# AJH_as3310_DUAL_ASR_03_4hp.net
KiCad netlist of a schematic drawn in EAGLE
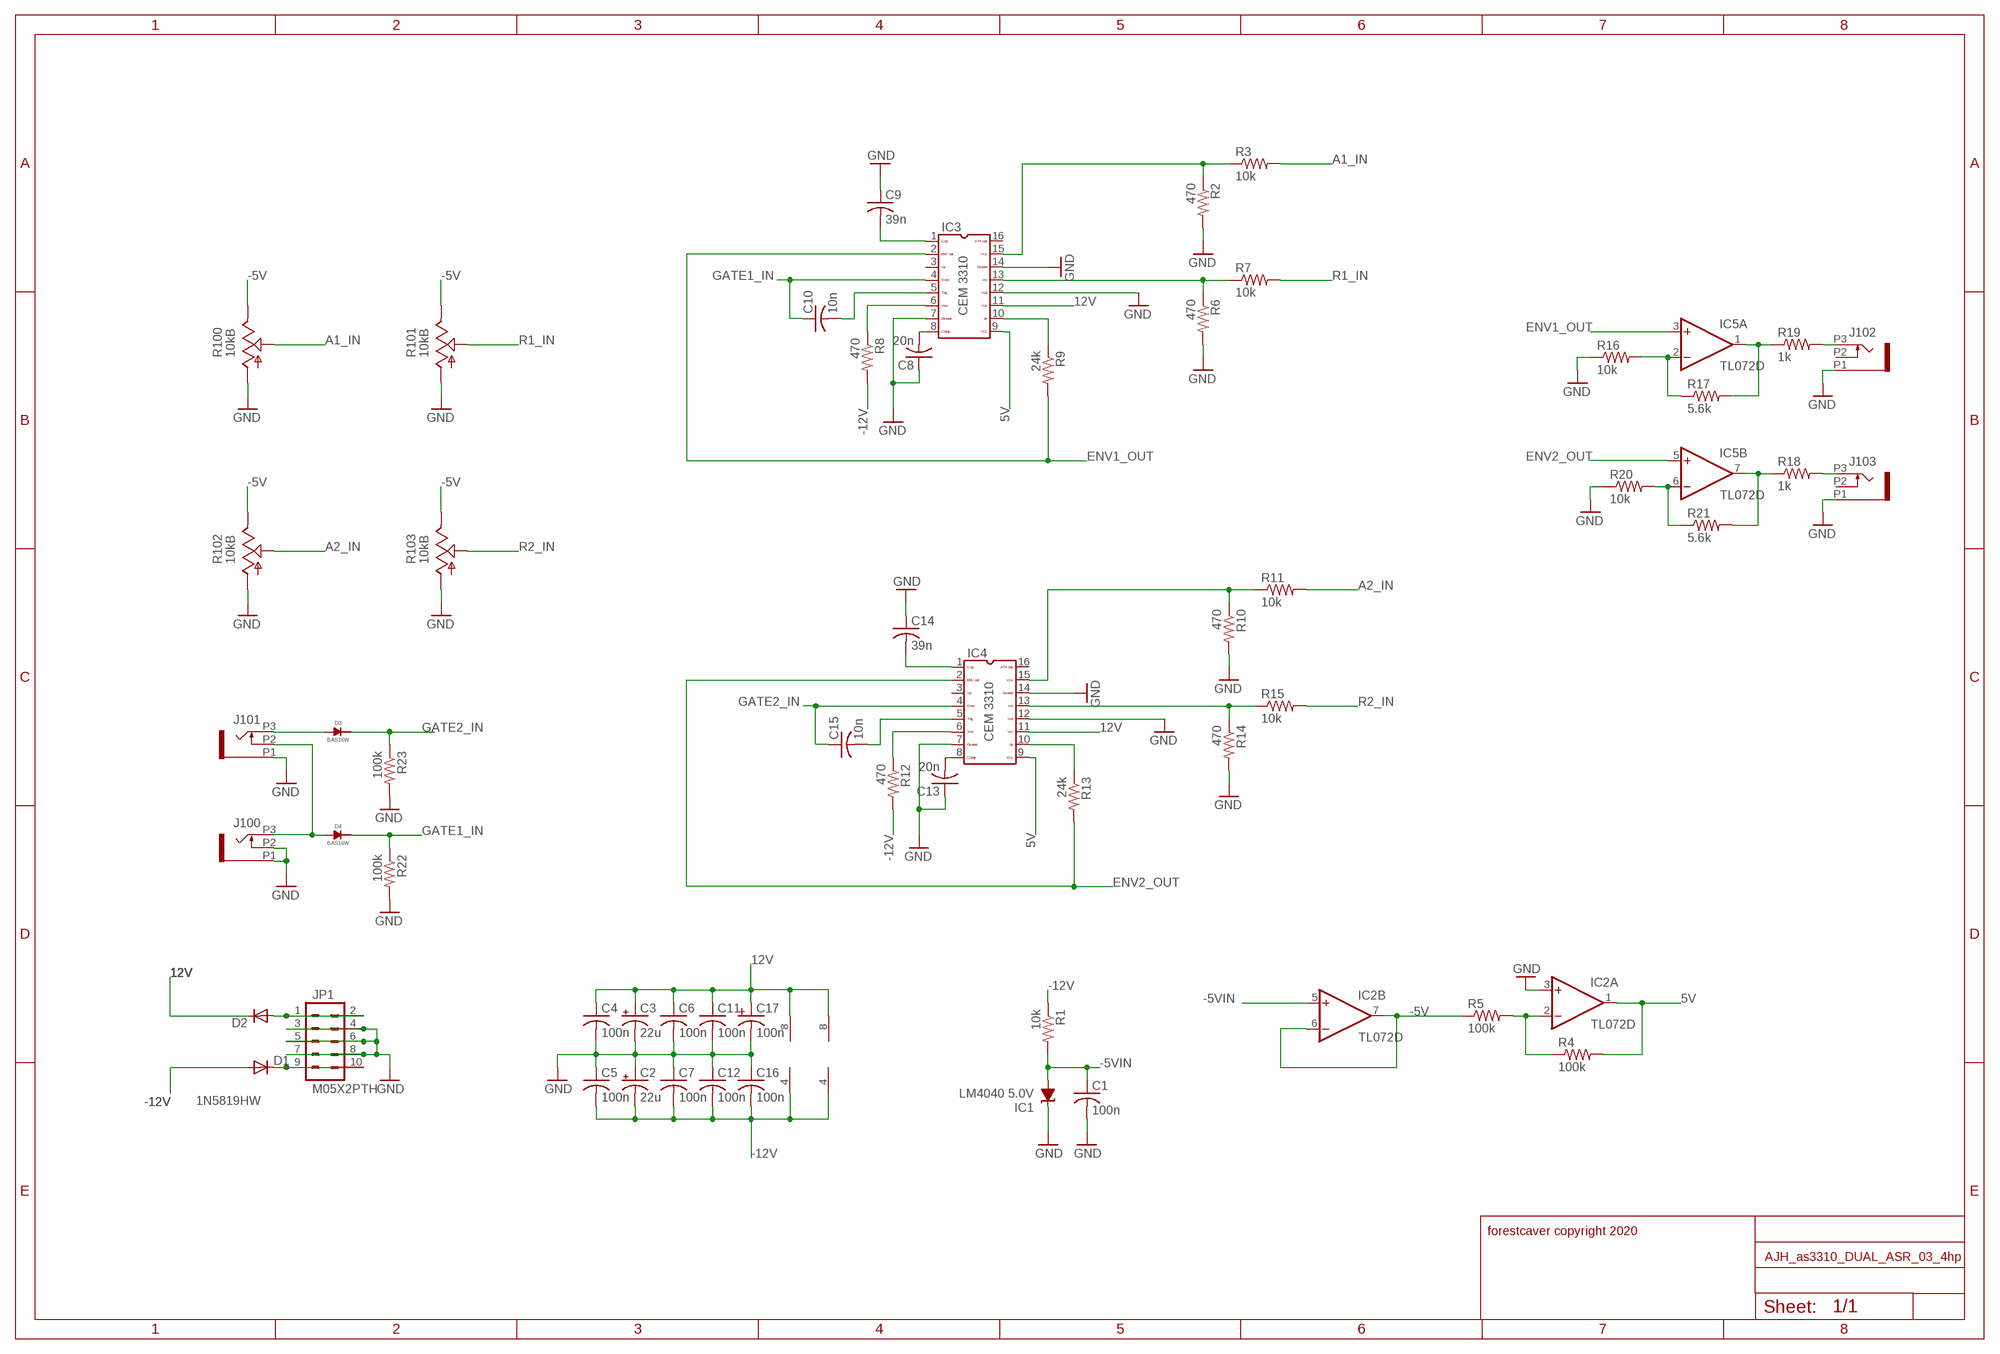
[diagram p0: schematic, sheet 1]

(export (version "E")
  (design (tool "Eeschema 10.0.6"))
  (components
    (comp (ref "C1")
      (value "100n")
      (footprint "eagle-import:C0603")
      (libsource (lib "eagle-import") (part "C-USC0603"))
    )
    (comp (ref "C2")
      (value "22u")
      (footprint "eagle-import:PANASONIC_B")
      (libsource (lib "eagle-import") (part "CPOL-USB"))
    )
    (comp (ref "C3")
      (value "22u")
      (footprint "eagle-import:PANASONIC_B")
      (libsource (lib "eagle-import") (part "CPOL-USB"))
    )
    (comp (ref "C4")
      (value "100n")
      (footprint "eagle-import:C0603")
      (libsource (lib "eagle-import") (part "C-USC0603"))
    )
    (comp (ref "C5")
      (value "100n")
      (footprint "eagle-import:C0603")
      (libsource (lib "eagle-import") (part "C-USC0603"))
    )
    (comp (ref "C6")
      (value "100n")
      (footprint "eagle-import:C0603")
      (libsource (lib "eagle-import") (part "C-USC0603"))
    )
    (comp (ref "C7")
      (value "100n")
      (footprint "eagle-import:C0603")
      (libsource (lib "eagle-import") (part "C-USC0603"))
    )
    (comp (ref "C8")
      (value "20n")
      (footprint "eagle-import:C0603")
      (libsource (lib "eagle-import") (part "C-USC0603"))
    )
    (comp (ref "C9")
      (value "39n")
      (footprint "eagle-import:C0603")
      (libsource (lib "eagle-import") (part "C-USC0603"))
    )
    (comp (ref "C10")
      (value "10n")
      (footprint "eagle-import:C0603")
      (libsource (lib "eagle-import") (part "C-USC0603"))
    )
    (comp (ref "C11")
      (value "100n")
      (footprint "eagle-import:C0603")
      (libsource (lib "eagle-import") (part "C-USC0603"))
    )
    (comp (ref "C12")
      (value "100n")
      (footprint "eagle-import:C0603")
      (libsource (lib "eagle-import") (part "C-USC0603"))
    )
    (comp (ref "C13")
      (value "20n")
      (footprint "eagle-import:C0603")
      (libsource (lib "eagle-import") (part "C-USC0603"))
    )
    (comp (ref "C14")
      (value "39n")
      (footprint "eagle-import:C0603")
      (libsource (lib "eagle-import") (part "C-USC0603"))
    )
    (comp (ref "C15")
      (value "10n")
      (footprint "eagle-import:C0603")
      (libsource (lib "eagle-import") (part "C-USC0603"))
    )
    (comp (ref "C16")
      (value "100n")
      (footprint "eagle-import:C0603")
      (libsource (lib "eagle-import") (part "C-USC0603"))
    )
    (comp (ref "C17")
      (value "100n")
      (footprint "eagle-import:C0603")
      (libsource (lib "eagle-import") (part "C-USC0603"))
    )
    (comp (ref "D1")
      (value "1N5819HW")
      (footprint "eagle-import:SOD123")
      (libsource (lib "eagle-import") (part "DIODE-SOD123"))
    )
    (comp (ref "D2")
      (value "1N5819HW")
      (footprint "eagle-import:SOD123")
      (libsource (lib "eagle-import") (part "DIODE-SOD123"))
    )
    (comp (ref "D3")
      (value "BAS16W")
      (footprint "eagle-import:SOT-323")
      (libsource (lib "eagle-import") (part "BAS16W"))
    )
    (comp (ref "D4")
      (value "BAS16W")
      (footprint "eagle-import:SOT-323")
      (libsource (lib "eagle-import") (part "BAS16W"))
    )
    (comp (ref "IC1")
      (value "LM4040 5.0V")
      (footprint "eagle-import:DBZ_R-PDSO-G3")
      (libsource (lib "eagle-import") (part "LM4041DBZC12"))
    )
    (comp (ref "IC2")
      (value "TL072D")
      (footprint "eagle-import:SO08")
      (libsource (lib "eagle-import") (part "TL072D"))
    )
    (comp (ref "IC3")
      (value "CEM3310SOIC16")
      (footprint "eagle-import:SO16")
      (libsource (lib "eagle-import") (part "CEM3310SOIC16"))
    )
    (comp (ref "IC4")
      (value "CEM3310SOIC16")
      (footprint "eagle-import:SO16")
      (libsource (lib "eagle-import") (part "CEM3310SOIC16"))
    )
    (comp (ref "IC5")
      (value "TL072D")
      (footprint "eagle-import:SO08")
      (libsource (lib "eagle-import") (part "TL072D"))
    )
    (comp (ref "J100")
      (value "PJ301_THONKICONN6")
      (footprint "eagle-import:WQP_PJ_301M6")
      (libsource (lib "eagle-import") (part "PJ301_THONKICONN6"))
    )
    (comp (ref "J101")
      (value "PJ301_THONKICONN6")
      (footprint "eagle-import:WQP_PJ_301M6")
      (libsource (lib "eagle-import") (part "PJ301_THONKICONN6"))
    )
    (comp (ref "J102")
      (value "PJ301_THONKICONN6")
      (footprint "eagle-import:WQP_PJ_301M6")
      (libsource (lib "eagle-import") (part "PJ301_THONKICONN6"))
    )
    (comp (ref "J103")
      (value "PJ301_THONKICONN6")
      (footprint "eagle-import:WQP_PJ_301M6")
      (libsource (lib "eagle-import") (part "PJ301_THONKICONN6"))
    )
    (comp (ref "JP1")
      (value "M05X2PTH")
      (footprint "eagle-import:AVR_ICSP")
      (libsource (lib "eagle-import") (part "M05X2PTH"))
    )
    (comp (ref "R1")
      (value "10k")
      (footprint "eagle-import:R0603")
      (libsource (lib "eagle-import") (part "R-US_R0603"))
    )
    (comp (ref "R2")
      (value "470")
      (footprint "eagle-import:R0603")
      (libsource (lib "eagle-import") (part "R-US_R0603"))
    )
    (comp (ref "R3")
      (value "10k")
      (footprint "eagle-import:R0603")
      (libsource (lib "eagle-import") (part "R-US_R0603"))
    )
    (comp (ref "R4")
      (value "100k")
      (footprint "eagle-import:R0603")
      (libsource (lib "eagle-import") (part "R-US_R0603"))
    )
    (comp (ref "R5")
      (value "100k")
      (footprint "eagle-import:R0603")
      (libsource (lib "eagle-import") (part "R-US_R0603"))
    )
    (comp (ref "R6")
      (value "470")
      (footprint "eagle-import:R0603")
      (libsource (lib "eagle-import") (part "R-US_R0603"))
    )
    (comp (ref "R7")
      (value "10k")
      (footprint "eagle-import:R0603")
      (libsource (lib "eagle-import") (part "R-US_R0603"))
    )
    (comp (ref "R8")
      (value "470")
      (footprint "eagle-import:R0603")
      (libsource (lib "eagle-import") (part "R-US_R0603"))
    )
    (comp (ref "R9")
      (value "24k")
      (footprint "eagle-import:R0603")
      (libsource (lib "eagle-import") (part "R-US_R0603"))
    )
    (comp (ref "R10")
      (value "470")
      (footprint "eagle-import:R0603")
      (libsource (lib "eagle-import") (part "R-US_R0603"))
    )
    (comp (ref "R11")
      (value "10k")
      (footprint "eagle-import:R0603")
      (libsource (lib "eagle-import") (part "R-US_R0603"))
    )
    (comp (ref "R12")
      (value "470")
      (footprint "eagle-import:R0603")
      (libsource (lib "eagle-import") (part "R-US_R0603"))
    )
    (comp (ref "R13")
      (value "24k")
      (footprint "eagle-import:R0603")
      (libsource (lib "eagle-import") (part "R-US_R0603"))
    )
    (comp (ref "R14")
      (value "470")
      (footprint "eagle-import:R0603")
      (libsource (lib "eagle-import") (part "R-US_R0603"))
    )
    (comp (ref "R15")
      (value "10k")
      (footprint "eagle-import:R0603")
      (libsource (lib "eagle-import") (part "R-US_R0603"))
    )
    (comp (ref "R16")
      (value "10k")
      (footprint "eagle-import:R0603")
      (libsource (lib "eagle-import") (part "R-US_R0603"))
    )
    (comp (ref "R17")
      (value "5.6k")
      (footprint "eagle-import:R0603")
      (libsource (lib "eagle-import") (part "R-US_R0603"))
    )
    (comp (ref "R18")
      (value "1k")
      (footprint "eagle-import:R0603")
      (libsource (lib "eagle-import") (part "R-US_R0603"))
    )
    (comp (ref "R19")
      (value "1k")
      (footprint "eagle-import:R0603")
      (libsource (lib "eagle-import") (part "R-US_R0603"))
    )
    (comp (ref "R20")
      (value "10k")
      (footprint "eagle-import:R0603")
      (libsource (lib "eagle-import") (part "R-US_R0603"))
    )
    (comp (ref "R21")
      (value "5.6k")
      (footprint "eagle-import:R0603")
      (libsource (lib "eagle-import") (part "R-US_R0603"))
    )
    (comp (ref "R22")
      (value "100k")
      (footprint "eagle-import:R0603")
      (libsource (lib "eagle-import") (part "R-US_R0603"))
    )
    (comp (ref "R23")
      (value "100k")
      (footprint "eagle-import:R0603")
      (libsource (lib "eagle-import") (part "R-US_R0603"))
    )
    (comp (ref "R100")
      (value "10kB")
      (footprint "eagle-import:ALPS_POT_VERTICAL")
      (libsource (lib "eagle-import") (part "POT_USVERTICAL"))
    )
    (comp (ref "R101")
      (value "10kB")
      (footprint "eagle-import:ALPS_POT_VERTICAL")
      (libsource (lib "eagle-import") (part "POT_USVERTICAL"))
    )
    (comp (ref "R102")
      (value "10kB")
      (footprint "eagle-import:ALPS_POT_VERTICAL")
      (libsource (lib "eagle-import") (part "POT_USVERTICAL"))
    )
    (comp (ref "R103")
      (value "10kB")
      (footprint "eagle-import:ALPS_POT_VERTICAL")
      (libsource (lib "eagle-import") (part "POT_USVERTICAL"))
    )
  )
  (nets
    (net (code "1") (name "/-5V") (class "Default")
      (node (ref "IC2") (pin "6") (pinfunction "-IN_6") (pintype "input"))
      (node (ref "IC2") (pin "7") (pinfunction "OUT_7") (pintype "output"))
      (node (ref "R100") (pin "P$1") (pinfunction "E_P$1") (pintype "passive"))
      (node (ref "R101") (pin "P$1") (pinfunction "E_P$1") (pintype "passive"))
      (node (ref "R102") (pin "P$1") (pinfunction "E_P$1") (pintype "passive"))
      (node (ref "R103") (pin "P$1") (pinfunction "E_P$1") (pintype "passive"))
      (node (ref "R5") (pin "1") (pinfunction "1_1") (pintype "passive"))
    )
    (net (code "2") (name "/-5VIN") (class "Default")
      (node (ref "C1") (pin "1") (pinfunction "1_1") (pintype "passive"))
      (node (ref "IC1") (pin "2") (pinfunction "A_2") (pintype "passive"))
      (node (ref "IC2") (pin "5") (pinfunction "+IN_5") (pintype "input"))
      (node (ref "R1") (pin "2") (pinfunction "2_2") (pintype "passive"))
    )
    (net (code "3") (name "/-12V") (class "Default")
      (node (ref "C12") (pin "2") (pinfunction "2_2") (pintype "passive"))
      (node (ref "C16") (pin "2") (pinfunction "2_2") (pintype "passive"))
      (node (ref "C2") (pin "-") (pinfunction "-_-") (pintype "passive"))
      (node (ref "C5") (pin "2") (pinfunction "2_2") (pintype "passive"))
      (node (ref "C7") (pin "2") (pinfunction "2_2") (pintype "passive"))
      (node (ref "D1") (pin "A") (pinfunction "A_A") (pintype "passive"))
      (node (ref "IC2") (pin "4") (pinfunction "V-_4") (pintype "power_in"))
      (node (ref "IC5") (pin "4") (pinfunction "V-_4") (pintype "power_in"))
      (node (ref "R1") (pin "1") (pinfunction "1_1") (pintype "passive"))
      (node (ref "R12") (pin "2") (pinfunction "2_2") (pintype "passive"))
      (node (ref "R8") (pin "2") (pinfunction "2_2") (pintype "passive"))
    )
    (net (code "4") (name "/5V") (class "Default")
      (node (ref "IC2") (pin "1") (pinfunction "OUT_1") (pintype "output"))
      (node (ref "IC3") (pin "9") (pinfunction "9_9") (pintype "power_in"))
      (node (ref "IC4") (pin "9") (pinfunction "9_9") (pintype "power_in"))
      (node (ref "R4") (pin "2") (pinfunction "2_2") (pintype "passive"))
    )
    (net (code "5") (name "/12V") (class "Default")
      (node (ref "C11") (pin "1") (pinfunction "1_1") (pintype "passive"))
      (node (ref "C17") (pin "1") (pinfunction "1_1") (pintype "passive"))
      (node (ref "C3") (pin "+") (pinfunction "+_+") (pintype "passive"))
      (node (ref "C4") (pin "1") (pinfunction "1_1") (pintype "passive"))
      (node (ref "C6") (pin "1") (pinfunction "1_1") (pintype "passive"))
      (node (ref "D2") (pin "C") (pinfunction "C_C") (pintype "passive"))
      (node (ref "IC2") (pin "8") (pinfunction "V+_8") (pintype "power_in"))
      (node (ref "IC3") (pin "11") (pinfunction "11_11") (pintype "power_in"))
      (node (ref "IC4") (pin "11") (pinfunction "11_11") (pintype "power_in"))
      (node (ref "IC5") (pin "8") (pinfunction "V+_8") (pintype "power_in"))
    )
    (net (code "6") (name "/A1_IN") (class "Default")
      (node (ref "R100") (pin "P$2") (pinfunction "S_P$2") (pintype "passive"))
      (node (ref "R3") (pin "2") (pinfunction "2_2") (pintype "passive"))
    )
    (net (code "7") (name "/A2_IN") (class "Default")
      (node (ref "R102") (pin "P$2") (pinfunction "S_P$2") (pintype "passive"))
      (node (ref "R11") (pin "2") (pinfunction "2_2") (pintype "passive"))
    )
    (net (code "8") (name "/ENV1_OUT") (class "Default")
      (node (ref "IC3") (pin "2") (pinfunction "2_2") (pintype "output"))
      (node (ref "IC5") (pin "3") (pinfunction "+IN_3") (pintype "input"))
      (node (ref "R9") (pin "2") (pinfunction "2_2") (pintype "passive"))
    )
    (net (code "9") (name "/ENV2_OUT") (class "Default")
      (node (ref "IC4") (pin "2") (pinfunction "2_2") (pintype "output"))
      (node (ref "IC5") (pin "5") (pinfunction "+IN_5") (pintype "input"))
      (node (ref "R13") (pin "2") (pinfunction "2_2") (pintype "passive"))
    )
    (net (code "10") (name "/GATE1_IN") (class "Default")
      (node (ref "C10") (pin "1") (pinfunction "1_1") (pintype "passive"))
      (node (ref "D4") (pin "CATHODE") (pinfunction "CATHODE_CATHODE") (pintype "bidirectional"))
      (node (ref "IC3") (pin "4") (pinfunction "4_4") (pintype "input"))
      (node (ref "R22") (pin "1") (pinfunction "1_1") (pintype "passive"))
    )
    (net (code "11") (name "/GATE2_IN") (class "Default")
      (node (ref "C15") (pin "1") (pinfunction "1_1") (pintype "passive"))
      (node (ref "D3") (pin "CATHODE") (pinfunction "CATHODE_CATHODE") (pintype "bidirectional"))
      (node (ref "IC4") (pin "4") (pinfunction "4_4") (pintype "input"))
      (node (ref "R23") (pin "1") (pinfunction "1_1") (pintype "passive"))
    )
    (net (code "12") (name "/R1_IN") (class "Default")
      (node (ref "R101") (pin "P$2") (pinfunction "S_P$2") (pintype "passive"))
      (node (ref "R7") (pin "2") (pinfunction "2_2") (pintype "passive"))
    )
    (net (code "13") (name "/R2_IN") (class "Default")
      (node (ref "R103") (pin "P$2") (pinfunction "S_P$2") (pintype "passive"))
      (node (ref "R15") (pin "2") (pinfunction "2_2") (pintype "passive"))
    )
    (net (code "14") (name "GND") (class "Default")
      (node (ref "C1") (pin "2") (pinfunction "2_2") (pintype "passive"))
      (node (ref "C11") (pin "2") (pinfunction "2_2") (pintype "passive"))
      (node (ref "C12") (pin "1") (pinfunction "1_1") (pintype "passive"))
      (node (ref "C13") (pin "1") (pinfunction "1_1") (pintype "passive"))
      (node (ref "C14") (pin "1") (pinfunction "1_1") (pintype "passive"))
      (node (ref "C16") (pin "1") (pinfunction "1_1") (pintype "passive"))
      (node (ref "C17") (pin "2") (pinfunction "2_2") (pintype "passive"))
      (node (ref "C2") (pin "+") (pinfunction "+_+") (pintype "passive"))
      (node (ref "C3") (pin "-") (pinfunction "-_-") (pintype "passive"))
      (node (ref "C4") (pin "2") (pinfunction "2_2") (pintype "passive"))
      (node (ref "C5") (pin "1") (pinfunction "1_1") (pintype "passive"))
      (node (ref "C6") (pin "2") (pinfunction "2_2") (pintype "passive"))
      (node (ref "C7") (pin "1") (pinfunction "1_1") (pintype "passive"))
      (node (ref "C8") (pin "1") (pinfunction "1_1") (pintype "passive"))
      (node (ref "C9") (pin "1") (pinfunction "1_1") (pintype "passive"))
      (node (ref "IC1") (pin "1") (pinfunction "C_1") (pintype "passive"))
      (node (ref "IC2") (pin "3") (pinfunction "+IN_3") (pintype "input"))
      (node (ref "IC3") (pin "12") (pinfunction "12_12") (pintype "power_in"))
      (node (ref "IC3") (pin "14") (pinfunction "14_14") (pintype "power_in"))
      (node (ref "IC3") (pin "7") (pinfunction "7_7") (pintype "power_in"))
      (node (ref "IC4") (pin "12") (pinfunction "12_12") (pintype "power_in"))
      (node (ref "IC4") (pin "14") (pinfunction "14_14") (pintype "power_in"))
      (node (ref "IC4") (pin "7") (pinfunction "7_7") (pintype "power_in"))
      (node (ref "J100") (pin "P1") (pinfunction "1_P1") (pintype "passive"))
      (node (ref "J100") (pin "P2") (pinfunction "2_P2") (pintype "passive"))
      (node (ref "J101") (pin "P1") (pinfunction "1_P1") (pintype "passive"))
      (node (ref "J102") (pin "P1") (pinfunction "1_P1") (pintype "passive"))
      (node (ref "J103") (pin "P1") (pinfunction "1_P1") (pintype "passive"))
      (node (ref "JP1") (pin "3") (pinfunction "3_3") (pintype "passive"))
      (node (ref "JP1") (pin "4") (pinfunction "4_4") (pintype "passive"))
      (node (ref "JP1") (pin "5") (pinfunction "5_5") (pintype "passive"))
      (node (ref "JP1") (pin "6") (pinfunction "6_6") (pintype "passive"))
      (node (ref "JP1") (pin "7") (pinfunction "7_7") (pintype "passive"))
      (node (ref "JP1") (pin "8") (pinfunction "8_8") (pintype "passive"))
      (node (ref "R10") (pin "2") (pinfunction "2_2") (pintype "passive"))
      (node (ref "R100") (pin "P$3") (pinfunction "A_P$3") (pintype "passive"))
      (node (ref "R101") (pin "P$3") (pinfunction "A_P$3") (pintype "passive"))
      (node (ref "R102") (pin "P$3") (pinfunction "A_P$3") (pintype "passive"))
      (node (ref "R103") (pin "P$3") (pinfunction "A_P$3") (pintype "passive"))
      (node (ref "R14") (pin "2") (pinfunction "2_2") (pintype "passive"))
      (node (ref "R16") (pin "1") (pinfunction "1_1") (pintype "passive"))
      (node (ref "R2") (pin "2") (pinfunction "2_2") (pintype "passive"))
      (node (ref "R20") (pin "1") (pinfunction "1_1") (pintype "passive"))
      (node (ref "R22") (pin "2") (pinfunction "2_2") (pintype "passive"))
      (node (ref "R23") (pin "2") (pinfunction "2_2") (pintype "passive"))
      (node (ref "R6") (pin "2") (pinfunction "2_2") (pintype "passive"))
    )
    (net (code "15") (name "Net-(C8-Pad2)") (class "Default")
      (node (ref "C8") (pin "2") (pinfunction "2_2") (pintype "passive"))
      (node (ref "IC3") (pin "8") (pinfunction "8_8") (pintype "bidirectional"))
    )
    (net (code "16") (name "Net-(C9-Pad2)") (class "Default")
      (node (ref "C9") (pin "2") (pinfunction "2_2") (pintype "passive"))
      (node (ref "IC3") (pin "1") (pinfunction "1_1") (pintype "bidirectional"))
    )
    (net (code "17") (name "Net-(C10-Pad2)") (class "Default")
      (node (ref "C10") (pin "2") (pinfunction "2_2") (pintype "passive"))
      (node (ref "IC3") (pin "5") (pinfunction "5_5") (pintype "input"))
    )
    (net (code "18") (name "Net-(C13-Pad2)") (class "Default")
      (node (ref "C13") (pin "2") (pinfunction "2_2") (pintype "passive"))
      (node (ref "IC4") (pin "8") (pinfunction "8_8") (pintype "bidirectional"))
    )
    (net (code "19") (name "Net-(C14-Pad2)") (class "Default")
      (node (ref "C14") (pin "2") (pinfunction "2_2") (pintype "passive"))
      (node (ref "IC4") (pin "1") (pinfunction "1_1") (pintype "bidirectional"))
    )
    (net (code "20") (name "Net-(C15-Pad2)") (class "Default")
      (node (ref "C15") (pin "2") (pinfunction "2_2") (pintype "passive"))
      (node (ref "IC4") (pin "5") (pinfunction "5_5") (pintype "input"))
    )
    (net (code "21") (name "Net-(D1-PadC)") (class "Default")
      (node (ref "D1") (pin "C") (pinfunction "C_C") (pintype "passive"))
      (node (ref "JP1") (pin "10") (pinfunction "10_10") (pintype "passive"))
      (node (ref "JP1") (pin "9") (pinfunction "9_9") (pintype "passive"))
    )
    (net (code "22") (name "Net-(D2-PadA)") (class "Default")
      (node (ref "D2") (pin "A") (pinfunction "A_A") (pintype "passive"))
      (node (ref "JP1") (pin "1") (pinfunction "1_1") (pintype "passive"))
      (node (ref "JP1") (pin "2") (pinfunction "2_2") (pintype "passive"))
    )
    (net (code "23") (name "Net-(IC2A--IN)") (class "Default")
      (node (ref "IC2") (pin "2") (pinfunction "-IN_2") (pintype "input"))
      (node (ref "R4") (pin "1") (pinfunction "1_1") (pintype "passive"))
      (node (ref "R5") (pin "2") (pinfunction "2_2") (pintype "passive"))
    )
    (net (code "24") (name "Net-(IC3-Pad6)") (class "Default")
      (node (ref "IC3") (pin "6") (pinfunction "6_6") (pintype "power_in"))
      (node (ref "R8") (pin "1") (pinfunction "1_1") (pintype "passive"))
    )
    (net (code "25") (name "Net-(IC3-Pad10)") (class "Default")
      (node (ref "IC3") (pin "10") (pinfunction "10_10") (pintype "power_in"))
      (node (ref "R9") (pin "1") (pinfunction "1_1") (pintype "passive"))
    )
    (net (code "26") (name "Net-(IC3-Pad13)") (class "Default")
      (node (ref "IC3") (pin "13") (pinfunction "13_13") (pintype "power_in"))
      (node (ref "R6") (pin "1") (pinfunction "1_1") (pintype "passive"))
      (node (ref "R7") (pin "1") (pinfunction "1_1") (pintype "passive"))
    )
    (net (code "27") (name "Net-(IC3-Pad15)") (class "Default")
      (node (ref "IC3") (pin "15") (pinfunction "15_15") (pintype "power_in"))
      (node (ref "R2") (pin "1") (pinfunction "1_1") (pintype "passive"))
      (node (ref "R3") (pin "1") (pinfunction "1_1") (pintype "passive"))
    )
    (net (code "28") (name "Net-(IC4-Pad6)") (class "Default")
      (node (ref "IC4") (pin "6") (pinfunction "6_6") (pintype "power_in"))
      (node (ref "R12") (pin "1") (pinfunction "1_1") (pintype "passive"))
    )
    (net (code "29") (name "Net-(IC4-Pad10)") (class "Default")
      (node (ref "IC4") (pin "10") (pinfunction "10_10") (pintype "power_in"))
      (node (ref "R13") (pin "1") (pinfunction "1_1") (pintype "passive"))
    )
    (net (code "30") (name "Net-(IC4-Pad13)") (class "Default")
      (node (ref "IC4") (pin "13") (pinfunction "13_13") (pintype "power_in"))
      (node (ref "R14") (pin "1") (pinfunction "1_1") (pintype "passive"))
      (node (ref "R15") (pin "1") (pinfunction "1_1") (pintype "passive"))
    )
    (net (code "31") (name "Net-(IC4-Pad15)") (class "Default")
      (node (ref "IC4") (pin "15") (pinfunction "15_15") (pintype "power_in"))
      (node (ref "R10") (pin "1") (pinfunction "1_1") (pintype "passive"))
      (node (ref "R11") (pin "1") (pinfunction "1_1") (pintype "passive"))
    )
    (net (code "32") (name "Net-(IC5A--IN)") (class "Default")
      (node (ref "IC5") (pin "2") (pinfunction "-IN_2") (pintype "input"))
      (node (ref "R16") (pin "2") (pinfunction "2_2") (pintype "passive"))
      (node (ref "R17") (pin "1") (pinfunction "1_1") (pintype "passive"))
    )
    (net (code "33") (name "Net-(IC5A-OUT)") (class "Default")
      (node (ref "IC5") (pin "1") (pinfunction "OUT_1") (pintype "output"))
      (node (ref "R17") (pin "2") (pinfunction "2_2") (pintype "passive"))
      (node (ref "R19") (pin "1") (pinfunction "1_1") (pintype "passive"))
    )
    (net (code "34") (name "Net-(IC5B--IN)") (class "Default")
      (node (ref "IC5") (pin "6") (pinfunction "-IN_6") (pintype "input"))
      (node (ref "R20") (pin "2") (pinfunction "2_2") (pintype "passive"))
      (node (ref "R21") (pin "1") (pinfunction "1_1") (pintype "passive"))
    )
    (net (code "35") (name "Net-(IC5B-OUT)") (class "Default")
      (node (ref "IC5") (pin "7") (pinfunction "OUT_7") (pintype "output"))
      (node (ref "R18") (pin "1") (pinfunction "1_1") (pintype "passive"))
      (node (ref "R21") (pin "2") (pinfunction "2_2") (pintype "passive"))
    )
    (net (code "36") (name "Net-(J100-3)") (class "Default")
      (node (ref "D4") (pin "ANODE") (pinfunction "ANODE_ANODE") (pintype "bidirectional"))
      (node (ref "J100") (pin "P3") (pinfunction "3_P3") (pintype "passive"))
      (node (ref "J101") (pin "P2") (pinfunction "2_P2") (pintype "passive"))
    )
    (net (code "37") (name "Net-(J101-3)") (class "Default")
      (node (ref "D3") (pin "ANODE") (pinfunction "ANODE_ANODE") (pintype "bidirectional"))
      (node (ref "J101") (pin "P3") (pinfunction "3_P3") (pintype "passive"))
    )
    (net (code "38") (name "Net-(J102-3)") (class "Default")
      (node (ref "J102") (pin "P3") (pinfunction "3_P3") (pintype "passive"))
      (node (ref "R19") (pin "2") (pinfunction "2_2") (pintype "passive"))
    )
    (net (code "39") (name "Net-(J103-3)") (class "Default")
      (node (ref "J103") (pin "P3") (pinfunction "3_P3") (pintype "passive"))
      (node (ref "R18") (pin "2") (pinfunction "2_2") (pintype "passive"))
    )
    (net (code "40") (name "unconnected-(IC3-Pad3)") (class "Default")
      (node (ref "IC3") (pin "3") (pinfunction "3_3") (pintype "bidirectional"))
    )
    (net (code "41") (name "unconnected-(IC3-Pad16)") (class "Default")
      (node (ref "IC3") (pin "16") (pinfunction "16_16") (pintype "output"))
    )
    (net (code "42") (name "unconnected-(IC4-Pad3)") (class "Default")
      (node (ref "IC4") (pin "3") (pinfunction "3_3") (pintype "bidirectional"))
    )
    (net (code "43") (name "unconnected-(IC4-Pad16)") (class "Default")
      (node (ref "IC4") (pin "16") (pinfunction "16_16") (pintype "output"))
    )
    (net (code "44") (name "unconnected-(J102-2-PadP2)") (class "Default")
      (node (ref "J102") (pin "P2") (pinfunction "2_P2") (pintype "passive"))
    )
    (net (code "45") (name "unconnected-(J103-2-PadP2)") (class "Default")
      (node (ref "J103") (pin "P2") (pinfunction "2_P2") (pintype "passive"))
    )
  )
)
